# nixie_drive_neo.net
KiCad netlist of a schematic drawn in EAGLE
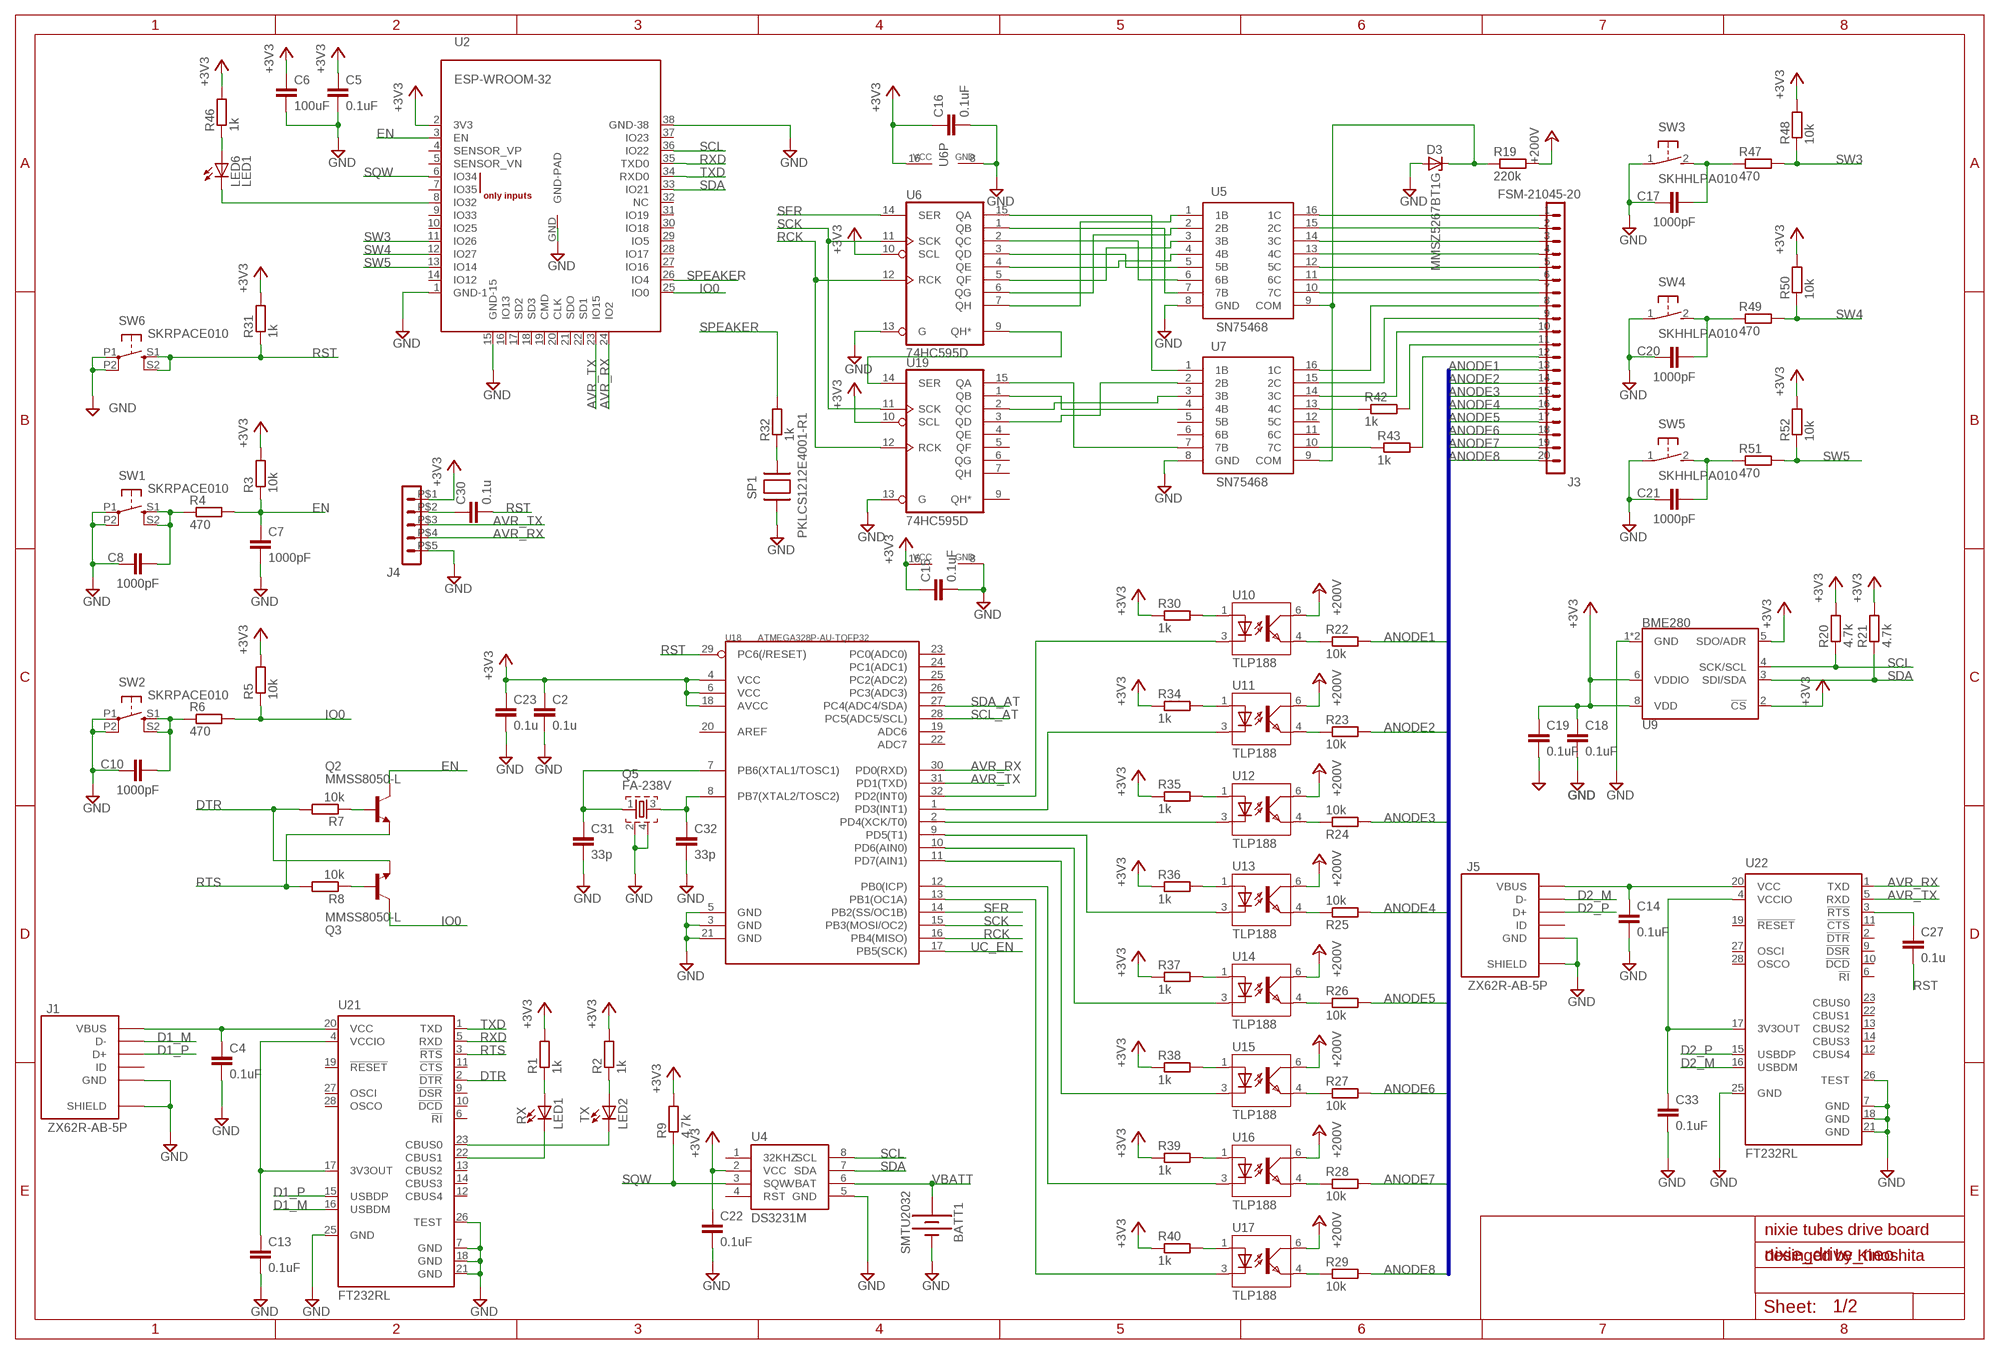
[diagram p0: schematic, sheet 1]
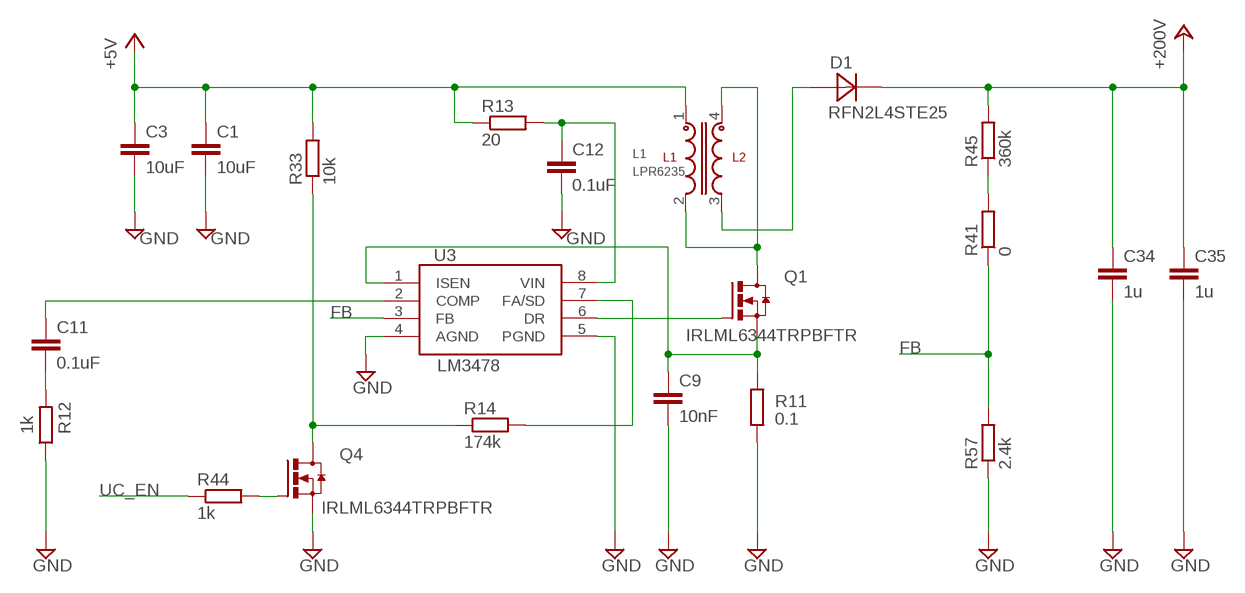
[diagram p1: schematic, sheet 2]

(export (version "E")
  (design (tool "Eeschema 10.0.6"))
  (components
    (comp (ref "BATT1")
      (value "SMTU2032")
      (footprint "eagle-import:SMTU2032")
      (libsource (lib "eagle-import") (part "SMTU2032"))
    )
    (comp (ref "C2")
      (value "0.1u")
      (footprint "eagle-import:C0603")
      (libsource (lib "eagle-import") (part "C-EUC0603"))
    )
    (comp (ref "C4")
      (value "0.1uF")
      (footprint "eagle-import:C0603")
      (libsource (lib "eagle-import") (part "C-EUC0603"))
    )
    (comp (ref "C5")
      (value "0.1uF")
      (footprint "eagle-import:C0603")
      (libsource (lib "eagle-import") (part "C-EUC0603"))
    )
    (comp (ref "C6")
      (value "100uF")
      (footprint "eagle-import:C1210")
      (libsource (lib "eagle-import") (part "C-EUC1210"))
    )
    (comp (ref "C7")
      (value "1000pF")
      (footprint "eagle-import:C0603")
      (libsource (lib "eagle-import") (part "C-EUC0603"))
    )
    (comp (ref "C8")
      (value "1000pF")
      (footprint "eagle-import:C0603")
      (libsource (lib "eagle-import") (part "C-EUC0603"))
    )
    (comp (ref "C10")
      (value "1000pF")
      (footprint "eagle-import:C0603")
      (libsource (lib "eagle-import") (part "C-EUC0603"))
    )
    (comp (ref "C13")
      (value "0.1uF")
      (footprint "eagle-import:C0603")
      (libsource (lib "eagle-import") (part "C-EUC0603"))
    )
    (comp (ref "C14")
      (value "0.1uF")
      (footprint "eagle-import:C0603")
      (libsource (lib "eagle-import") (part "C-EUC0603"))
    )
    (comp (ref "C15")
      (value "0.1uF")
      (footprint "eagle-import:C0603")
      (libsource (lib "eagle-import") (part "C-EUC0603"))
    )
    (comp (ref "C16")
      (value "0.1uF")
      (footprint "eagle-import:C0603")
      (libsource (lib "eagle-import") (part "C-EUC0603"))
    )
    (comp (ref "C17")
      (value "1000pF")
      (footprint "eagle-import:C0603")
      (libsource (lib "eagle-import") (part "C-EUC0603"))
    )
    (comp (ref "C18")
      (value "0.1uF")
      (footprint "eagle-import:C0603")
      (libsource (lib "eagle-import") (part "C-EUC0603"))
    )
    (comp (ref "C19")
      (value "0.1uF")
      (footprint "eagle-import:C0603")
      (libsource (lib "eagle-import") (part "C-EUC0603"))
    )
    (comp (ref "C20")
      (value "1000pF")
      (footprint "eagle-import:C0603")
      (libsource (lib "eagle-import") (part "C-EUC0603"))
    )
    (comp (ref "C21")
      (value "1000pF")
      (footprint "eagle-import:C0603")
      (libsource (lib "eagle-import") (part "C-EUC0603"))
    )
    (comp (ref "C22")
      (value "0.1uF")
      (footprint "eagle-import:C0603")
      (libsource (lib "eagle-import") (part "C-EUC0603"))
    )
    (comp (ref "C23")
      (value "0.1u")
      (footprint "eagle-import:C0603")
      (libsource (lib "eagle-import") (part "C-EUC0603"))
    )
    (comp (ref "C27")
      (value "0.1u")
      (footprint "eagle-import:C0603")
      (libsource (lib "eagle-import") (part "C-EUC0603"))
    )
    (comp (ref "C30")
      (value "0.1u")
      (footprint "eagle-import:C0603")
      (libsource (lib "eagle-import") (part "C-EUC0603"))
    )
    (comp (ref "C31")
      (value "33p")
      (footprint "eagle-import:C0603")
      (libsource (lib "eagle-import") (part "C-EUC0603"))
    )
    (comp (ref "C32")
      (value "33p")
      (footprint "eagle-import:C0603")
      (libsource (lib "eagle-import") (part "C-EUC0603"))
    )
    (comp (ref "C33")
      (value "0.1uF")
      (footprint "eagle-import:C0603")
      (libsource (lib "eagle-import") (part "C-EUC0603"))
    )
    (comp (ref "D3")
      (value "MMSZ5267BT1G")
      (footprint "eagle-import:SOD123")
      (libsource (lib "eagle-import") (part "MMSZ5267BT1G"))
    )
    (comp (ref "J1")
      (value "ZX62R-AB-5P")
      (footprint "eagle-import:ZX62R-B-5PA")
      (libsource (lib "eagle-import") (part "ZX62R-AB-5P"))
    )
    (comp (ref "J3")
      (value "FSM-21045-20")
      (footprint "eagle-import:FSM-21045-20")
      (libsource (lib "eagle-import") (part "FSM-21045-20"))
    )
    (comp (ref "J4")
      (value "PIN_HEADER_MALE_1X05_05P")
      (footprint "eagle-import:PIN_HEADER_MALE_1X05_05P")
      (libsource (lib "eagle-import") (part "PIN_HEADER_MALE_1X05_05P"))
    )
    (comp (ref "J5")
      (value "ZX62R-AB-5P")
      (footprint "eagle-import:ZX62R-B-5PA")
      (libsource (lib "eagle-import") (part "ZX62R-AB-5P"))
    )
    (comp (ref "LED1")
      (value "RX")
      (footprint "eagle-import:CHIPLED_0603")
      (libsource (lib "eagle-import") (part "LEDCHIPLED_0603"))
    )
    (comp (ref "LED2")
      (value "TX")
      (footprint "eagle-import:CHIPLED_0603")
      (libsource (lib "eagle-import") (part "LEDCHIPLED_0603"))
    )
    (comp (ref "LED6")
      (value "LED1")
      (footprint "eagle-import:CHIPLED_0603")
      (libsource (lib "eagle-import") (part "LEDCHIPLED_0603"))
    )
    (comp (ref "Q2")
      (value "MMSS8050-L")
      (footprint "eagle-import:SOT23")
      (libsource (lib "eagle-import") (part "MMSS8050-L"))
    )
    (comp (ref "Q3")
      (value "MMSS8050-L")
      (footprint "eagle-import:SOT23")
      (libsource (lib "eagle-import") (part "MMSS8050-L"))
    )
    (comp (ref "Q5")
      (value "FA-238V")
      (footprint "eagle-import:FA238-V")
      (libsource (lib "eagle-import") (part "FA-238V"))
    )
    (comp (ref "R1")
      (value "1k")
      (footprint "eagle-import:R0603")
      (libsource (lib "eagle-import") (part "taki-library_R-EU_R0603"))
    )
    (comp (ref "R2")
      (value "1k")
      (footprint "eagle-import:R0603")
      (libsource (lib "eagle-import") (part "taki-library_R-EU_R0603"))
    )
    (comp (ref "R3")
      (value "10k")
      (footprint "eagle-import:R0603")
      (libsource (lib "eagle-import") (part "taki-library_R-EU_R0603"))
    )
    (comp (ref "R4")
      (value "470")
      (footprint "eagle-import:R0603")
      (libsource (lib "eagle-import") (part "taki-library_R-EU_R0603"))
    )
    (comp (ref "R5")
      (value "10k")
      (footprint "eagle-import:R0603")
      (libsource (lib "eagle-import") (part "taki-library_R-EU_R0603"))
    )
    (comp (ref "R6")
      (value "470")
      (footprint "eagle-import:R0603")
      (libsource (lib "eagle-import") (part "taki-library_R-EU_R0603"))
    )
    (comp (ref "R7")
      (value "10k")
      (footprint "eagle-import:R0603")
      (libsource (lib "eagle-import") (part "taki-library_R-EU_R0603"))
    )
    (comp (ref "R8")
      (value "10k")
      (footprint "eagle-import:R0603")
      (libsource (lib "eagle-import") (part "taki-library_R-EU_R0603"))
    )
    (comp (ref "R9")
      (value "4.7k")
      (footprint "eagle-import:R0603")
      (libsource (lib "eagle-import") (part "taki-library_R-EU_R0603"))
    )
    (comp (ref "R19")
      (value "220k")
      (footprint "eagle-import:R0603")
      (libsource (lib "eagle-import") (part "taki-library_R-EU_R0603"))
    )
    (comp (ref "R20")
      (value "4.7k")
      (footprint "eagle-import:R0603")
      (libsource (lib "eagle-import") (part "taki-library_R-EU_R0603"))
    )
    (comp (ref "R21")
      (value "4.7k")
      (footprint "eagle-import:R0603")
      (libsource (lib "eagle-import") (part "taki-library_R-EU_R0603"))
    )
    (comp (ref "R22")
      (value "10k")
      (footprint "eagle-import:R3216")
      (libsource (lib "eagle-import") (part "taki-library_R-EU_R3216"))
    )
    (comp (ref "R23")
      (value "10k")
      (footprint "eagle-import:R3216")
      (libsource (lib "eagle-import") (part "taki-library_R-EU_R3216"))
    )
    (comp (ref "R24")
      (value "10k")
      (footprint "eagle-import:R3216")
      (libsource (lib "eagle-import") (part "taki-library_R-EU_R3216"))
    )
    (comp (ref "R25")
      (value "10k")
      (footprint "eagle-import:R3216")
      (libsource (lib "eagle-import") (part "taki-library_R-EU_R3216"))
    )
    (comp (ref "R26")
      (value "10k")
      (footprint "eagle-import:R3216")
      (libsource (lib "eagle-import") (part "taki-library_R-EU_R3216"))
    )
    (comp (ref "R27")
      (value "10k")
      (footprint "eagle-import:R3216")
      (libsource (lib "eagle-import") (part "taki-library_R-EU_R3216"))
    )
    (comp (ref "R28")
      (value "10k")
      (footprint "eagle-import:R3216")
      (libsource (lib "eagle-import") (part "taki-library_R-EU_R3216"))
    )
    (comp (ref "R29")
      (value "10k")
      (footprint "eagle-import:R3216")
      (libsource (lib "eagle-import") (part "taki-library_R-EU_R3216"))
    )
    (comp (ref "R30")
      (value "1k")
      (footprint "eagle-import:R0603")
      (libsource (lib "eagle-import") (part "R-EU_R0603"))
    )
    (comp (ref "R31")
      (value "1k")
      (footprint "eagle-import:R0603")
      (libsource (lib "eagle-import") (part "taki-library_R-EU_R0603"))
    )
    (comp (ref "R32")
      (value "1k")
      (footprint "eagle-import:R0603")
      (libsource (lib "eagle-import") (part "taki-library_R-EU_R0603"))
    )
    (comp (ref "R34")
      (value "1k")
      (footprint "eagle-import:R0603")
      (libsource (lib "eagle-import") (part "R-EU_R0603"))
    )
    (comp (ref "R35")
      (value "1k")
      (footprint "eagle-import:R0603")
      (libsource (lib "eagle-import") (part "R-EU_R0603"))
    )
    (comp (ref "R36")
      (value "1k")
      (footprint "eagle-import:R0603")
      (libsource (lib "eagle-import") (part "R-EU_R0603"))
    )
    (comp (ref "R37")
      (value "1k")
      (footprint "eagle-import:R0603")
      (libsource (lib "eagle-import") (part "R-EU_R0603"))
    )
    (comp (ref "R38")
      (value "1k")
      (footprint "eagle-import:R0603")
      (libsource (lib "eagle-import") (part "R-EU_R0603"))
    )
    (comp (ref "R39")
      (value "1k")
      (footprint "eagle-import:R0603")
      (libsource (lib "eagle-import") (part "R-EU_R0603"))
    )
    (comp (ref "R40")
      (value "1k")
      (footprint "eagle-import:R0603")
      (libsource (lib "eagle-import") (part "R-EU_R0603"))
    )
    (comp (ref "R42")
      (value "1k")
      (footprint "eagle-import:R0603")
      (libsource (lib "eagle-import") (part "R-EU_R0603"))
    )
    (comp (ref "R43")
      (value "1k")
      (footprint "eagle-import:R0603")
      (libsource (lib "eagle-import") (part "R-EU_R0603"))
    )
    (comp (ref "R46")
      (value "1k")
      (footprint "eagle-import:R0603")
      (libsource (lib "eagle-import") (part "taki-library_R-EU_R0603"))
    )
    (comp (ref "R47")
      (value "470")
      (footprint "eagle-import:R0603")
      (libsource (lib "eagle-import") (part "taki-library_R-EU_R0603"))
    )
    (comp (ref "R48")
      (value "10k")
      (footprint "eagle-import:R0603")
      (libsource (lib "eagle-import") (part "taki-library_R-EU_R0603"))
    )
    (comp (ref "R49")
      (value "470")
      (footprint "eagle-import:R0603")
      (libsource (lib "eagle-import") (part "taki-library_R-EU_R0603"))
    )
    (comp (ref "R50")
      (value "10k")
      (footprint "eagle-import:R0603")
      (libsource (lib "eagle-import") (part "taki-library_R-EU_R0603"))
    )
    (comp (ref "R51")
      (value "470")
      (footprint "eagle-import:R0603")
      (libsource (lib "eagle-import") (part "taki-library_R-EU_R0603"))
    )
    (comp (ref "R52")
      (value "10k")
      (footprint "eagle-import:R0603")
      (libsource (lib "eagle-import") (part "taki-library_R-EU_R0603"))
    )
    (comp (ref "SP1")
      (value "PKLCS1212E4001-R1")
      (footprint "eagle-import:PKLCS1212E4001-R1")
      (libsource (lib "eagle-import") (part "PKLCS1212E4001-R1"))
    )
    (comp (ref "SW1")
      (value "SKRPACE010")
      (footprint "eagle-import:SKRPACE010")
      (libsource (lib "eagle-import") (part "SKRPACE010"))
    )
    (comp (ref "SW2")
      (value "SKRPACE010")
      (footprint "eagle-import:SKRPACE010")
      (libsource (lib "eagle-import") (part "SKRPACE010"))
    )
    (comp (ref "SW3")
      (value "SKHHLPA010")
      (footprint "eagle-import:SKHHLPA010")
      (libsource (lib "eagle-import") (part "SKHHLPA010"))
    )
    (comp (ref "SW4")
      (value "SKHHLPA010")
      (footprint "eagle-import:SKHHLPA010")
      (libsource (lib "eagle-import") (part "SKHHLPA010"))
    )
    (comp (ref "SW5")
      (value "SKHHLPA010")
      (footprint "eagle-import:SKHHLPA010")
      (libsource (lib "eagle-import") (part "SKHHLPA010"))
    )
    (comp (ref "SW6")
      (value "SKRPACE010")
      (footprint "eagle-import:SKRPACE010")
      (libsource (lib "eagle-import") (part "SKRPACE010"))
    )
    (comp (ref "U2")
      (value "ESP-WROOM-32")
      (footprint "eagle-import:ESP-WROOM-32")
      (libsource (lib "eagle-import") (part "ESP-WROOM-32"))
    )
    (comp (ref "U4")
      (value "DS3231M")
      (footprint "eagle-import:SO08")
      (libsource (lib "eagle-import") (part "DS3231M"))
    )
    (comp (ref "U5")
      (value "SN75468")
      (footprint "eagle-import:R-PDSO-G16")
      (libsource (lib "eagle-import") (part "SN75468"))
    )
    (comp (ref "U6")
      (value "74HC595D")
      (footprint "eagle-import:SO16")
      (libsource (lib "eagle-import") (part "74595DHC"))
    )
    (comp (ref "U7")
      (value "SN75468")
      (footprint "eagle-import:R-PDSO-G16")
      (libsource (lib "eagle-import") (part "SN75468"))
    )
    (comp (ref "U9")
      (value "BME280")
      (footprint "eagle-import:LGA-8-2.5X2.5")
      (libsource (lib "eagle-import") (part "BME280"))
    )
    (comp (ref "U10")
      (value "TLP188")
      (footprint "eagle-import:11-4M1S")
      (libsource (lib "eagle-import") (part "TLP188"))
    )
    (comp (ref "U11")
      (value "TLP188")
      (footprint "eagle-import:11-4M1S")
      (libsource (lib "eagle-import") (part "TLP188"))
    )
    (comp (ref "U12")
      (value "TLP188")
      (footprint "eagle-import:11-4M1S")
      (libsource (lib "eagle-import") (part "TLP188"))
    )
    (comp (ref "U13")
      (value "TLP188")
      (footprint "eagle-import:11-4M1S")
      (libsource (lib "eagle-import") (part "TLP188"))
    )
    (comp (ref "U14")
      (value "TLP188")
      (footprint "eagle-import:11-4M1S")
      (libsource (lib "eagle-import") (part "TLP188"))
    )
    (comp (ref "U15")
      (value "TLP188")
      (footprint "eagle-import:11-4M1S")
      (libsource (lib "eagle-import") (part "TLP188"))
    )
    (comp (ref "U16")
      (value "TLP188")
      (footprint "eagle-import:11-4M1S")
      (libsource (lib "eagle-import") (part "TLP188"))
    )
    (comp (ref "U17")
      (value "TLP188")
      (footprint "eagle-import:11-4M1S")
      (libsource (lib "eagle-import") (part "TLP188"))
    )
    (comp (ref "U18")
      (value "ATMEGA328P-AU-TQFP32")
      (footprint "eagle-import:TQFP32-0.8-7X7MM")
      (fields (field (name "MPN") "ATMEGA328P-AU"))
      (libsource (lib "eagle-import") (part "MCU-ATMEGA328P-AU(TQFP32)"))
    )
    (comp (ref "U19")
      (value "74HC595D")
      (footprint "eagle-import:SO16")
      (libsource (lib "eagle-import") (part "74595DHC"))
    )
    (comp (ref "U21")
      (value "FT232RL")
      (footprint "eagle-import:SSOP28")
      (libsource (lib "eagle-import") (part "FT232RL"))
    )
    (comp (ref "U22")
      (value "FT232RL")
      (footprint "eagle-import:SSOP28")
      (libsource (lib "eagle-import") (part "FT232RL"))
    )
    (comp (ref "C1")
      (value "10uF")
      (footprint "eagle-import:C0603")
      (libsource (lib "eagle-import") (part "C-EUC0603"))
    )
    (comp (ref "C3")
      (value "10uF")
      (footprint "eagle-import:C0603")
      (libsource (lib "eagle-import") (part "C-EUC0603"))
    )
    (comp (ref "C9")
      (value "10nF")
      (footprint "eagle-import:C0603")
      (libsource (lib "eagle-import") (part "C-EUC0603"))
    )
    (comp (ref "C11")
      (value "0.1uF")
      (footprint "eagle-import:C0603")
      (libsource (lib "eagle-import") (part "C-EUC0603"))
    )
    (comp (ref "C12")
      (value "0.1uF")
      (footprint "eagle-import:C0603")
      (libsource (lib "eagle-import") (part "C-EUC0603"))
    )
    (comp (ref "C34")
      (value "1u")
      (footprint "eagle-import:C5750")
      (libsource (lib "eagle-import") (part "C-EU"))
    )
    (comp (ref "C35")
      (value "1u")
      (footprint "eagle-import:C5750")
      (libsource (lib "eagle-import") (part "C-EU"))
    )
    (comp (ref "D1")
      (value "RFN2L4STE25")
      (footprint "eagle-import:SOD-106")
      (libsource (lib "eagle-import") (part "RFN2L4STE25"))
    )
    (comp (ref "L1")
      (value "LPR6235")
      (footprint "eagle-import:LPR6235")
      (libsource (lib "eagle-import") (part "LPR6235"))
    )
    (comp (ref "Q1")
      (value "IRLML6344TRPBFTR")
      (footprint "eagle-import:SOT23-N-MOSFET")
      (libsource (lib "eagle-import") (part "IRLML6344TRPBFTR"))
    )
    (comp (ref "Q4")
      (value "IRLML6344TRPBFTR")
      (footprint "eagle-import:SOT23-N-MOSFET")
      (libsource (lib "eagle-import") (part "IRLML6344TRPBFTR"))
    )
    (comp (ref "R11")
      (value "0.1")
      (footprint "eagle-import:R0603")
      (libsource (lib "eagle-import") (part "taki-library_R-EU_R0603"))
    )
    (comp (ref "R12")
      (value "1k")
      (footprint "eagle-import:R0603")
      (libsource (lib "eagle-import") (part "taki-library_R-EU_R0603"))
    )
    (comp (ref "R13")
      (value "20")
      (footprint "eagle-import:R0603")
      (libsource (lib "eagle-import") (part "taki-library_R-EU_R0603"))
    )
    (comp (ref "R14")
      (value "174k")
      (footprint "eagle-import:R0603")
      (libsource (lib "eagle-import") (part "taki-library_R-EU_R0603"))
    )
    (comp (ref "R33")
      (value "10k")
      (footprint "eagle-import:R0603")
      (libsource (lib "eagle-import") (part "taki-library_R-EU_R0603"))
    )
    (comp (ref "R41")
      (value "0")
      (footprint "eagle-import:R0603")
      (libsource (lib "eagle-import") (part "taki-library_R-EU_R0603"))
    )
    (comp (ref "R44")
      (value "1k")
      (footprint "eagle-import:R0603")
      (libsource (lib "eagle-import") (part "taki-library_R-EU_R0603"))
    )
    (comp (ref "R45")
      (value "360k")
      (footprint "eagle-import:R0603")
      (libsource (lib "eagle-import") (part "taki-library_R-EU_R0603"))
    )
    (comp (ref "R57")
      (value "2.4k")
      (footprint "eagle-import:R0603")
      (libsource (lib "eagle-import") (part "taki-library_R-EU_R0603"))
    )
    (comp (ref "U3")
      (value "LM3478")
      (footprint "eagle-import:SOIC8-LT")
      (libsource (lib "eagle-import") (part "LM3478"))
    )
  )
  (nets
    (net (code "1") (name "+3V3") (class "Default")
      (node (ref "C15") (pin "1") (pinfunction "1_1") (pintype "passive"))
      (node (ref "C16") (pin "1") (pinfunction "1_1") (pintype "passive"))
      (node (ref "C18") (pin "1") (pinfunction "1_1") (pintype "passive"))
      (node (ref "C19") (pin "1") (pinfunction "1_1") (pintype "passive"))
      (node (ref "C2") (pin "1") (pinfunction "1_1") (pintype "passive"))
      (node (ref "C22") (pin "1") (pinfunction "1_1") (pintype "passive"))
      (node (ref "C23") (pin "1") (pinfunction "1_1") (pintype "passive"))
      (node (ref "C5") (pin "1") (pinfunction "1_1") (pintype "passive"))
      (node (ref "C6") (pin "1") (pinfunction "1_1") (pintype "passive"))
      (node (ref "J4") (pin "P$1") (pinfunction "1_P$1") (pintype "bidirectional"))
      (node (ref "R1") (pin "2") (pinfunction "2_2") (pintype "passive"))
      (node (ref "R2") (pin "2") (pinfunction "2_2") (pintype "passive"))
      (node (ref "R20") (pin "2") (pinfunction "2_2") (pintype "passive"))
      (node (ref "R21") (pin "2") (pinfunction "2_2") (pintype "passive"))
      (node (ref "R3") (pin "2") (pinfunction "2_2") (pintype "passive"))
      (node (ref "R30") (pin "1") (pinfunction "1_1") (pintype "passive"))
      (node (ref "R31") (pin "2") (pinfunction "2_2") (pintype "passive"))
      (node (ref "R34") (pin "1") (pinfunction "1_1") (pintype "passive"))
      (node (ref "R35") (pin "1") (pinfunction "1_1") (pintype "passive"))
      (node (ref "R36") (pin "1") (pinfunction "1_1") (pintype "passive"))
      (node (ref "R37") (pin "1") (pinfunction "1_1") (pintype "passive"))
      (node (ref "R38") (pin "1") (pinfunction "1_1") (pintype "passive"))
      (node (ref "R39") (pin "1") (pinfunction "1_1") (pintype "passive"))
      (node (ref "R40") (pin "1") (pinfunction "1_1") (pintype "passive"))
      (node (ref "R46") (pin "2") (pinfunction "2_2") (pintype "passive"))
      (node (ref "R48") (pin "2") (pinfunction "2_2") (pintype "passive"))
      (node (ref "R5") (pin "2") (pinfunction "2_2") (pintype "passive"))
      (node (ref "R50") (pin "2") (pinfunction "2_2") (pintype "passive"))
      (node (ref "R52") (pin "2") (pinfunction "2_2") (pintype "passive"))
      (node (ref "R9") (pin "2") (pinfunction "2_2") (pintype "passive"))
      (node (ref "U18") (pin "18") (pinfunction "AVCC_18") (pintype "bidirectional"))
      (node (ref "U18") (pin "4") (pinfunction "VCC_4") (pintype "bidirectional"))
      (node (ref "U18") (pin "6") (pinfunction "VCC_6") (pintype "bidirectional"))
      (node (ref "U19") (pin "10") (pinfunction "SCL_10") (pintype "input"))
      (node (ref "U19") (pin "16") (pinfunction "VCC_16") (pintype "power_in"))
      (node (ref "U2") (pin "2") (pinfunction "3V3_2") (pintype "bidirectional"))
      (node (ref "U4") (pin "2") (pinfunction "VCC_2") (pintype "power_in"))
      (node (ref "U6") (pin "10") (pinfunction "SCL_10") (pintype "input"))
      (node (ref "U6") (pin "16") (pinfunction "VCC_16") (pintype "power_in"))
      (node (ref "U9") (pin "2") (pinfunction "~{CS}_2") (pintype "bidirectional"))
      (node (ref "U9") (pin "5") (pinfunction "SDO/ADR_5") (pintype "bidirectional"))
      (node (ref "U9") (pin "6") (pinfunction "VDDIO_6") (pintype "bidirectional"))
      (node (ref "U9") (pin "8") (pinfunction "VDD_8") (pintype "bidirectional"))
    )
    (net (code "2") (name "+5V") (class "Default")
      (node (ref "C1") (pin "1") (pinfunction "1_1") (pintype "passive"))
      (node (ref "C3") (pin "1") (pinfunction "1_1") (pintype "passive"))
      (node (ref "L1") (pin "1") (pinfunction "1_1") (pintype "bidirectional"))
      (node (ref "R13") (pin "1") (pinfunction "1_1") (pintype "passive"))
      (node (ref "R33") (pin "2") (pinfunction "2_2") (pintype "passive"))
    )
    (net (code "3") (name "+200V") (class "Default")
      (node (ref "C34") (pin "1") (pinfunction "1_1") (pintype "passive"))
      (node (ref "C35") (pin "1") (pinfunction "1_1") (pintype "passive"))
      (node (ref "D1") (pin "K") (pinfunction "C_K") (pintype "passive"))
      (node (ref "R19") (pin "2") (pinfunction "2_2") (pintype "passive"))
      (node (ref "R45") (pin "2") (pinfunction "2_2") (pintype "passive"))
      (node (ref "U10") (pin "6") (pinfunction "COL_6") (pintype "passive"))
      (node (ref "U11") (pin "6") (pinfunction "COL_6") (pintype "passive"))
      (node (ref "U12") (pin "6") (pinfunction "COL_6") (pintype "passive"))
      (node (ref "U13") (pin "6") (pinfunction "COL_6") (pintype "passive"))
      (node (ref "U14") (pin "6") (pinfunction "COL_6") (pintype "passive"))
      (node (ref "U15") (pin "6") (pinfunction "COL_6") (pintype "passive"))
      (node (ref "U16") (pin "6") (pinfunction "COL_6") (pintype "passive"))
      (node (ref "U17") (pin "6") (pinfunction "COL_6") (pintype "passive"))
    )
    (net (code "4") (name "ANODE1") (class "Default")
      (node (ref "J3") (pin "13") (pinfunction "13_13") (pintype "bidirectional"))
      (node (ref "R22") (pin "2") (pinfunction "2_2") (pintype "passive"))
    )
    (net (code "5") (name "ANODE2") (class "Default")
      (node (ref "J3") (pin "14") (pinfunction "14_14") (pintype "bidirectional"))
      (node (ref "R23") (pin "2") (pinfunction "2_2") (pintype "passive"))
    )
    (net (code "6") (name "ANODE3") (class "Default")
      (node (ref "J3") (pin "15") (pinfunction "15_15") (pintype "bidirectional"))
      (node (ref "R24") (pin "2") (pinfunction "2_2") (pintype "passive"))
    )
    (net (code "7") (name "ANODE4") (class "Default")
      (node (ref "J3") (pin "16") (pinfunction "16_16") (pintype "bidirectional"))
      (node (ref "R25") (pin "2") (pinfunction "2_2") (pintype "passive"))
    )
    (net (code "8") (name "ANODE5") (class "Default")
      (node (ref "J3") (pin "17") (pinfunction "17_17") (pintype "bidirectional"))
      (node (ref "R26") (pin "2") (pinfunction "2_2") (pintype "passive"))
    )
    (net (code "9") (name "ANODE6") (class "Default")
      (node (ref "J3") (pin "18") (pinfunction "18_18") (pintype "bidirectional"))
      (node (ref "R27") (pin "2") (pinfunction "2_2") (pintype "passive"))
    )
    (net (code "10") (name "ANODE7") (class "Default")
      (node (ref "J3") (pin "19") (pinfunction "19_19") (pintype "bidirectional"))
      (node (ref "R28") (pin "2") (pinfunction "2_2") (pintype "passive"))
    )
    (net (code "11") (name "ANODE8") (class "Default")
      (node (ref "J3") (pin "20") (pinfunction "20_20") (pintype "bidirectional"))
      (node (ref "R29") (pin "2") (pinfunction "2_2") (pintype "passive"))
    )
    (net (code "12") (name "AVR_RX") (class "Default")
      (node (ref "J4") (pin "P$4") (pinfunction "4_P$4") (pintype "bidirectional"))
      (node (ref "U18") (pin "30") (pinfunction "PD0(RXD)_30") (pintype "bidirectional"))
      (node (ref "U2") (pin "24") (pinfunction "IO2_24") (pintype "bidirectional"))
      (node (ref "U22") (pin "1") (pinfunction "TXD_1") (pintype "output"))
    )
    (net (code "13") (name "AVR_TX") (class "Default")
      (node (ref "J4") (pin "P$3") (pinfunction "3_P$3") (pintype "bidirectional"))
      (node (ref "U18") (pin "31") (pinfunction "PD1(TXD)_31") (pintype "bidirectional"))
      (node (ref "U2") (pin "23") (pinfunction "IO15_23") (pintype "bidirectional"))
      (node (ref "U22") (pin "5") (pinfunction "RXD_5") (pintype "input"))
    )
    (net (code "14") (name "D1_M") (class "Default")
      (node (ref "J1") (pin "D-") (pinfunction "D-_D-") (pintype "bidirectional"))
      (node (ref "U21") (pin "16") (pinfunction "USBDM_16") (pintype "bidirectional"))
    )
    (net (code "15") (name "D1_P") (class "Default")
      (node (ref "J1") (pin "D+") (pinfunction "D+_D+") (pintype "bidirectional"))
      (node (ref "U21") (pin "15") (pinfunction "USBDP_15") (pintype "bidirectional"))
    )
    (net (code "16") (name "D2_M") (class "Default")
      (node (ref "J5") (pin "D-") (pinfunction "D-_D-") (pintype "bidirectional"))
      (node (ref "U22") (pin "16") (pinfunction "USBDM_16") (pintype "bidirectional"))
    )
    (net (code "17") (name "D2_P") (class "Default")
      (node (ref "J5") (pin "D+") (pinfunction "D+_D+") (pintype "bidirectional"))
      (node (ref "U22") (pin "15") (pinfunction "USBDP_15") (pintype "bidirectional"))
    )
    (net (code "18") (name "DTR") (class "Default")
      (node (ref "Q3") (pin "E") (pinfunction "E_E") (pintype "passive"))
      (node (ref "R7") (pin "2") (pinfunction "2_2") (pintype "passive"))
      (node (ref "U21") (pin "2") (pinfunction "~{DTR}_2") (pintype "output"))
    )
    (net (code "19") (name "EN") (class "Default")
      (node (ref "C7") (pin "1") (pinfunction "1_1") (pintype "passive"))
      (node (ref "Q2") (pin "C") (pinfunction "C_C") (pintype "passive"))
      (node (ref "R3") (pin "1") (pinfunction "1_1") (pintype "passive"))
      (node (ref "R4") (pin "2") (pinfunction "2_2") (pintype "passive"))
      (node (ref "U2") (pin "3") (pinfunction "EN_3") (pintype "bidirectional"))
    )
    (net (code "20") (name "FB") (class "Default")
      (node (ref "R41") (pin "1") (pinfunction "1_1") (pintype "passive"))
      (node (ref "R57") (pin "2") (pinfunction "2_2") (pintype "passive"))
      (node (ref "U3") (pin "3") (pinfunction "FB_3") (pintype "bidirectional"))
    )
    (net (code "21") (name "GND") (class "Default")
      (node (ref "BATT1") (pin "N") (pinfunction "-_N") (pintype "power_in"))
      (node (ref "C1") (pin "2") (pinfunction "2_2") (pintype "passive"))
      (node (ref "C10") (pin "1") (pinfunction "1_1") (pintype "passive"))
      (node (ref "C12") (pin "2") (pinfunction "2_2") (pintype "passive"))
      (node (ref "C13") (pin "2") (pinfunction "2_2") (pintype "passive"))
      (node (ref "C14") (pin "2") (pinfunction "2_2") (pintype "passive"))
      (node (ref "C15") (pin "2") (pinfunction "2_2") (pintype "passive"))
      (node (ref "C16") (pin "2") (pinfunction "2_2") (pintype "passive"))
      (node (ref "C17") (pin "1") (pinfunction "1_1") (pintype "passive"))
      (node (ref "C18") (pin "2") (pinfunction "2_2") (pintype "passive"))
      (node (ref "C19") (pin "2") (pinfunction "2_2") (pintype "passive"))
      (node (ref "C2") (pin "2") (pinfunction "2_2") (pintype "passive"))
      (node (ref "C20") (pin "1") (pinfunction "1_1") (pintype "passive"))
      (node (ref "C21") (pin "1") (pinfunction "1_1") (pintype "passive"))
      (node (ref "C22") (pin "2") (pinfunction "2_2") (pintype "passive"))
      (node (ref "C23") (pin "2") (pinfunction "2_2") (pintype "passive"))
      (node (ref "C3") (pin "2") (pinfunction "2_2") (pintype "passive"))
      (node (ref "C31") (pin "2") (pinfunction "2_2") (pintype "passive"))
      (node (ref "C32") (pin "2") (pinfunction "2_2") (pintype "passive"))
      (node (ref "C33") (pin "2") (pinfunction "2_2") (pintype "passive"))
      (node (ref "C34") (pin "2") (pinfunction "2_2") (pintype "passive"))
      (node (ref "C35") (pin "2") (pinfunction "2_2") (pintype "passive"))
      (node (ref "C4") (pin "2") (pinfunction "2_2") (pintype "passive"))
      (node (ref "C5") (pin "2") (pinfunction "2_2") (pintype "passive"))
      (node (ref "C6") (pin "2") (pinfunction "2_2") (pintype "passive"))
      (node (ref "C7") (pin "2") (pinfunction "2_2") (pintype "passive"))
      (node (ref "C8") (pin "1") (pinfunction "1_1") (pintype "passive"))
      (node (ref "C9") (pin "2") (pinfunction "2_2") (pintype "passive"))
      (node (ref "D3") (pin "A") (pinfunction "A_A") (pintype "passive"))
      (node (ref "J1") (pin "GND") (pinfunction "GND_GND") (pintype "bidirectional"))
      (node (ref "J1") (pin "SHIELD@1") (pinfunction "SHIELD_SHIELD@1") (pintype "bidirectional"))
      (node (ref "J1") (pin "SHIELD@2") (pinfunction "SHIELD_SHIELD@2") (pintype "bidirectional"))
      (node (ref "J1") (pin "SHIELD@3") (pinfunction "SHIELD_SHIELD@3") (pintype "bidirectional"))
      (node (ref "J1") (pin "SHIELD@4") (pinfunction "SHIELD_SHIELD@4") (pintype "bidirectional"))
      (node (ref "J4") (pin "P$5") (pinfunction "5_P$5") (pintype "bidirectional"))
      (node (ref "J5") (pin "GND") (pinfunction "GND_GND") (pintype "bidirectional"))
      (node (ref "J5") (pin "SHIELD@1") (pinfunction "SHIELD_SHIELD@1") (pintype "bidirectional"))
      (node (ref "J5") (pin "SHIELD@2") (pinfunction "SHIELD_SHIELD@2") (pintype "bidirectional"))
      (node (ref "J5") (pin "SHIELD@3") (pinfunction "SHIELD_SHIELD@3") (pintype "bidirectional"))
      (node (ref "J5") (pin "SHIELD@4") (pinfunction "SHIELD_SHIELD@4") (pintype "bidirectional"))
      (node (ref "Q4") (pin "S") (pinfunction "S_S") (pintype "passive"))
      (node (ref "Q5") (pin "2") (pinfunction "2_2") (pintype "passive"))
      (node (ref "Q5") (pin "4") (pinfunction "4_4") (pintype "passive"))
      (node (ref "R11") (pin "1") (pinfunction "1_1") (pintype "passive"))
      (node (ref "R12") (pin "1") (pinfunction "1_1") (pintype "passive"))
      (node (ref "R57") (pin "1") (pinfunction "1_1") (pintype "passive"))
      (node (ref "SP1") (pin "2") (pinfunction "P$2_2") (pintype "bidirectional"))
      (node (ref "SW1") (pin "P1") (pinfunction "P_P1") (pintype "passive"))
      (node (ref "SW1") (pin "P2") (pinfunction "P1_P2") (pintype "passive"))
      (node (ref "SW2") (pin "P1") (pinfunction "P_P1") (pintype "passive"))
      (node (ref "SW2") (pin "P2") (pinfunction "P1_P2") (pintype "passive"))
      (node (ref "SW3") (pin "1") (pinfunction "1_1") (pintype "passive"))
      (node (ref "SW4") (pin "1") (pinfunction "1_1") (pintype "passive"))
      (node (ref "SW5") (pin "1") (pinfunction "1_1") (pintype "passive"))
      (node (ref "SW6") (pin "P1") (pinfunction "P_P1") (pintype "passive"))
      (node (ref "SW6") (pin "P2") (pinfunction "P1_P2") (pintype "passive"))
      (node (ref "U18") (pin "21") (pinfunction "GND_21") (pintype "bidirectional"))
      (node (ref "U18") (pin "3") (pinfunction "GND_3") (pintype "bidirectional"))
      (node (ref "U18") (pin "5") (pinfunction "GND_5") (pintype "bidirectional"))
      (node (ref "U19") (pin "13") (pinfunction "G_13") (pintype "input"))
      (node (ref "U19") (pin "8") (pinfunction "GND_8") (pintype "power_in"))
      (node (ref "U2") (pin "1") (pinfunction "GND-1_1") (pintype "bidirectional"))
      (node (ref "U2") (pin "15") (pinfunction "GND-15_15") (pintype "bidirectional"))
      (node (ref "U2") (pin "38") (pinfunction "GND-38_38") (pintype "bidirectional"))
      (node (ref "U2") (pin "GND") (pinfunction "GND-PAD_GND") (pintype "bidirectional"))
      (node (ref "U21") (pin "18") (pinfunction "GND_18") (pintype "power_in"))
      (node (ref "U21") (pin "21") (pinfunction "GND_21") (pintype "power_in"))
      (node (ref "U21") (pin "25") (pinfunction "GND_25") (pintype "power_in"))
      (node (ref "U21") (pin "26") (pinfunction "TEST_26") (pintype "input"))
      (node (ref "U21") (pin "7") (pinfunction "GND_7") (pintype "power_in"))
      (node (ref "U22") (pin "18") (pinfunction "GND_18") (pintype "power_in"))
      (node (ref "U22") (pin "21") (pinfunction "GND_21") (pintype "power_in"))
      (node (ref "U22") (pin "25") (pinfunction "GND_25") (pintype "power_in"))
      (node (ref "U22") (pin "26") (pinfunction "TEST_26") (pintype "input"))
      (node (ref "U22") (pin "7") (pinfunction "GND_7") (pintype "power_in"))
      (node (ref "U3") (pin "4") (pinfunction "AGND_4") (pintype "bidirectional"))
      (node (ref "U3") (pin "5") (pinfunction "PGND_5") (pintype "bidirectional"))
      (node (ref "U4") (pin "5") (pinfunction "GND_5") (pintype "power_in"))
      (node (ref "U5") (pin "8") (pinfunction "GND_8") (pintype "bidirectional"))
      (node (ref "U6") (pin "13") (pinfunction "G_13") (pintype "input"))
      (node (ref "U6") (pin "8") (pinfunction "GND_8") (pintype "power_in"))
      (node (ref "U7") (pin "8") (pinfunction "GND_8") (pintype "bidirectional"))
      (node (ref "U9") (pin "1") (pinfunction "GND_1") (pintype "bidirectional"))
      (node (ref "U9") (pin "7") (pinfunction "GND_7") (pintype "bidirectional"))
    )
    (net (code "22") (name "IO0") (class "Default")
      (node (ref "Q3") (pin "C") (pinfunction "C_C") (pintype "passive"))
      (node (ref "R5") (pin "1") (pinfunction "1_1") (pintype "passive"))
      (node (ref "R6") (pin "2") (pinfunction "2_2") (pintype "passive"))
      (node (ref "U2") (pin "25") (pinfunction "IO0_25") (pintype "bidirectional"))
    )
    (net (code "23") (name "Net-(C11-Pad2)") (class "Default")
      (node (ref "C11") (pin "2") (pinfunction "2_2") (pintype "passive"))
      (node (ref "R12") (pin "2") (pinfunction "2_2") (pintype "passive"))
    )
    (net (code "24") (name "Net-(C17-Pad2)") (class "Default")
      (node (ref "C17") (pin "2") (pinfunction "2_2") (pintype "passive"))
      (node (ref "R47") (pin "1") (pinfunction "1_1") (pintype "passive"))
      (node (ref "SW3") (pin "2") (pinfunction "2_2") (pintype "passive"))
    )
    (net (code "25") (name "Net-(C20-Pad2)") (class "Default")
      (node (ref "C20") (pin "2") (pinfunction "2_2") (pintype "passive"))
      (node (ref "R49") (pin "1") (pinfunction "1_1") (pintype "passive"))
      (node (ref "SW4") (pin "2") (pinfunction "2_2") (pintype "passive"))
    )
    (net (code "26") (name "Net-(C21-Pad2)") (class "Default")
      (node (ref "C21") (pin "2") (pinfunction "2_2") (pintype "passive"))
      (node (ref "R51") (pin "1") (pinfunction "1_1") (pintype "passive"))
      (node (ref "SW5") (pin "2") (pinfunction "2_2") (pintype "passive"))
    )
    (net (code "27") (name "Net-(D1-PadA)") (class "Default")
      (node (ref "D1") (pin "A") (pinfunction "A_A") (pintype "passive"))
      (node (ref "L1") (pin "3") (pinfunction "3_3") (pintype "bidirectional"))
    )
    (net (code "28") (name "Net-(D3-C)") (class "Default")
      (node (ref "D3") (pin "K") (pinfunction "C_K") (pintype "passive"))
      (node (ref "R19") (pin "1") (pinfunction "1_1") (pintype "passive"))
      (node (ref "U5") (pin "9") (pinfunction "COM_9") (pintype "bidirectional"))
      (node (ref "U7") (pin "9") (pinfunction "COM_9") (pintype "bidirectional"))
    )
    (net (code "29") (name "Net-(J1-VBUS)") (class "Default")
      (node (ref "C4") (pin "1") (pinfunction "1_1") (pintype "passive"))
      (node (ref "J1") (pin "VCC") (pinfunction "VBUS_VCC") (pintype "bidirectional"))
      (node (ref "U21") (pin "20") (pinfunction "VCC_20") (pintype "power_in"))
    )
    (net (code "30") (name "Net-(J3-Pad11)") (class "Default")
      (node (ref "J3") (pin "11") (pinfunction "11_11") (pintype "bidirectional"))
      (node (ref "R42") (pin "2") (pinfunction "2_2") (pintype "passive"))
    )
    (net (code "31") (name "Net-(J3-Pad12)") (class "Default")
      (node (ref "J3") (pin "12") (pinfunction "12_12") (pintype "bidirectional"))
      (node (ref "R43") (pin "2") (pinfunction "2_2") (pintype "passive"))
    )
    (net (code "32") (name "Net-(J4-2)") (class "Default")
      (node (ref "C30") (pin "1") (pinfunction "1_1") (pintype "passive"))
      (node (ref "J4") (pin "P$2") (pinfunction "2_P$2") (pintype "bidirectional"))
    )
    (net (code "33") (name "Net-(J5-VBUS)") (class "Default")
      (node (ref "C14") (pin "1") (pinfunction "1_1") (pintype "passive"))
      (node (ref "J5") (pin "VCC") (pinfunction "VBUS_VCC") (pintype "bidirectional"))
      (node (ref "U22") (pin "20") (pinfunction "VCC_20") (pintype "power_in"))
    )
    (net (code "34") (name "Net-(L1-Pad2)") (class "Default")
      (node (ref "L1") (pin "2") (pinfunction "2_2") (pintype "bidirectional"))
      (node (ref "L1") (pin "4") (pinfunction "4_4") (pintype "bidirectional"))
      (node (ref "Q1") (pin "D") (pinfunction "D_D") (pintype "passive"))
    )
    (net (code "35") (name "Net-(LED1-PadA)") (class "Default")
      (node (ref "LED1") (pin "A") (pinfunction "A_A") (pintype "passive"))
      (node (ref "R1") (pin "1") (pinfunction "1_1") (pintype "passive"))
    )
    (net (code "36") (name "Net-(LED2-PadA)") (class "Default")
      (node (ref "LED2") (pin "A") (pinfunction "A_A") (pintype "passive"))
      (node (ref "R2") (pin "1") (pinfunction "1_1") (pintype "passive"))
    )
    (net (code "37") (name "Net-(LED6-PadA)") (class "Default")
      (node (ref "LED6") (pin "A") (pinfunction "A_A") (pintype "passive"))
      (node (ref "R46") (pin "1") (pinfunction "1_1") (pintype "passive"))
    )
    (net (code "38") (name "Net-(Q2-PadB)") (class "Default")
      (node (ref "Q2") (pin "B") (pinfunction "B_B") (pintype "passive"))
      (node (ref "R7") (pin "1") (pinfunction "1_1") (pintype "passive"))
    )
    (net (code "39") (name "Net-(Q3-PadB)") (class "Default")
      (node (ref "Q3") (pin "B") (pinfunction "B_B") (pintype "passive"))
      (node (ref "R8") (pin "1") (pinfunction "1_1") (pintype "passive"))
    )
    (net (code "40") (name "Net-(Q4-PadD)") (class "Default")
      (node (ref "Q4") (pin "D") (pinfunction "D_D") (pintype "passive"))
      (node (ref "R14") (pin "1") (pinfunction "1_1") (pintype "passive"))
      (node (ref "R33") (pin "1") (pinfunction "1_1") (pintype "passive"))
    )
    (net (code "41") (name "Net-(Q4-PadG)") (class "Default")
      (node (ref "Q4") (pin "G") (pinfunction "G_G") (pintype "passive"))
      (node (ref "R44") (pin "2") (pinfunction "2_2") (pintype "passive"))
    )
    (net (code "42") (name "Net-(R32-Pad1)") (class "Default")
      (node (ref "R32") (pin "1") (pinfunction "1_1") (pintype "passive"))
      (node (ref "SP1") (pin "1") (pinfunction "1_1") (pintype "bidirectional"))
    )
    (net (code "43") (name "Net-(R41-Pad2)") (class "Default")
      (node (ref "R41") (pin "2") (pinfunction "2_2") (pintype "passive"))
      (node (ref "R45") (pin "1") (pinfunction "1_1") (pintype "passive"))
    )
    (net (code "44") (name "Net-(SW1-S)") (class "Default")
      (node (ref "C8") (pin "2") (pinfunction "2_2") (pintype "passive"))
      (node (ref "R4") (pin "1") (pinfunction "1_1") (pintype "passive"))
      (node (ref "SW1") (pin "S1") (pinfunction "S_S1") (pintype "passive"))
      (node (ref "SW1") (pin "S2") (pinfunction "S1_S2") (pintype "passive"))
    )
    (net (code "45") (name "Net-(SW2-S)") (class "Default")
      (node (ref "C10") (pin "2") (pinfunction "2_2") (pintype "passive"))
      (node (ref "R6") (pin "1") (pinfunction "1_1") (pintype "passive"))
      (node (ref "SW2") (pin "S1") (pinfunction "S_S1") (pintype "passive"))
      (node (ref "SW2") (pin "S2") (pinfunction "S1_S2") (pintype "passive"))
    )
    (net (code "46") (name "Net-(U2-IO32)") (class "Default")
      (node (ref "LED6") (pin "C") (pinfunction "C_C") (pintype "passive"))
      (node (ref "U2") (pin "8") (pinfunction "IO32_8") (pintype "bidirectional"))
    )
    (net (code "47") (name "Net-(U3-COMP)") (class "Default")
      (node (ref "C11") (pin "1") (pinfunction "1_1") (pintype "passive"))
      (node (ref "U3") (pin "2") (pinfunction "COMP_2") (pintype "bidirectional"))
    )
    (net (code "48") (name "Net-(U3-DR)") (class "Default")
      (node (ref "Q1") (pin "G") (pinfunction "G_G") (pintype "passive"))
      (node (ref "U3") (pin "6") (pinfunction "DR_6") (pintype "bidirectional"))
    )
    (net (code "49") (name "Net-(U3-FA{slash}SD)") (class "Default")
      (node (ref "R14") (pin "2") (pinfunction "2_2") (pintype "passive"))
      (node (ref "U3") (pin "7") (pinfunction "FA/SD_7") (pintype "bidirectional"))
    )
    (net (code "50") (name "Net-(U3-ISEN)") (class "Default")
      (node (ref "C9") (pin "1") (pinfunction "1_1") (pintype "passive"))
      (node (ref "Q1") (pin "S") (pinfunction "S_S") (pintype "passive"))
      (node (ref "R11") (pin "2") (pinfunction "2_2") (pintype "passive"))
      (node (ref "U3") (pin "1") (pinfunction "ISEN_1") (pintype "bidirectional"))
    )
    (net (code "51") (name "Net-(U3-VIN)") (class "Default")
      (node (ref "C12") (pin "1") (pinfunction "1_1") (pintype "passive"))
      (node (ref "R13") (pin "2") (pinfunction "2_2") (pintype "passive"))
      (node (ref "U3") (pin "8") (pinfunction "VIN_8") (pintype "bidirectional"))
    )
    (net (code "52") (name "Net-(U5-1B)") (class "Default")
      (node (ref "U5") (pin "1") (pinfunction "1B_1") (pintype "bidirectional"))
      (node (ref "U6") (pin "7") (pinfunction "QH_7") (pintype "tri_state"))
    )
    (net (code "53") (name "Net-(U5-1C)") (class "Default")
      (node (ref "J3") (pin "1") (pinfunction "1_1") (pintype "bidirectional"))
      (node (ref "U5") (pin "16") (pinfunction "1C_16") (pintype "bidirectional"))
    )
    (net (code "54") (name "Net-(U5-2B)") (class "Default")
      (node (ref "U5") (pin "2") (pinfunction "2B_2") (pintype "bidirectional"))
      (node (ref "U6") (pin "6") (pinfunction "QG_6") (pintype "tri_state"))
    )
    (net (code "55") (name "Net-(U5-2C)") (class "Default")
      (node (ref "J3") (pin "2") (pinfunction "2_2") (pintype "bidirectional"))
      (node (ref "U5") (pin "15") (pinfunction "2C_15") (pintype "bidirectional"))
    )
    (net (code "56") (name "Net-(U5-3B)") (class "Default")
      (node (ref "U5") (pin "3") (pinfunction "3B_3") (pintype "bidirectional"))
      (node (ref "U6") (pin "5") (pinfunction "QF_5") (pintype "tri_state"))
    )
    (net (code "57") (name "Net-(U5-3C)") (class "Default")
      (node (ref "J3") (pin "3") (pinfunction "3_3") (pintype "bidirectional"))
      (node (ref "U5") (pin "14") (pinfunction "3C_14") (pintype "bidirectional"))
    )
    (net (code "58") (name "Net-(U5-4B)") (class "Default")
      (node (ref "U5") (pin "4") (pinfunction "4B_4") (pintype "bidirectional"))
      (node (ref "U6") (pin "4") (pinfunction "QE_4") (pintype "tri_state"))
    )
    (net (code "59") (name "Net-(U5-4C)") (class "Default")
      (node (ref "J3") (pin "4") (pinfunction "4_4") (pintype "bidirectional"))
      (node (ref "U5") (pin "13") (pinfunction "4C_13") (pintype "bidirectional"))
    )
    (net (code "60") (name "Net-(U5-5B)") (class "Default")
      (node (ref "U5") (pin "5") (pinfunction "5B_5") (pintype "bidirectional"))
      (node (ref "U6") (pin "3") (pinfunction "QD_3") (pintype "tri_state"))
    )
    (net (code "61") (name "Net-(U5-5C)") (class "Default")
      (node (ref "J3") (pin "5") (pinfunction "5_5") (pintype "bidirectional"))
      (node (ref "U5") (pin "12") (pinfunction "5C_12") (pintype "bidirectional"))
    )
    (net (code "62") (name "Net-(U5-6B)") (class "Default")
      (node (ref "U5") (pin "6") (pinfunction "6B_6") (pintype "bidirectional"))
      (node (ref "U6") (pin "2") (pinfunction "QC_2") (pintype "tri_state"))
    )
    (net (code "63") (name "Net-(U5-6C)") (class "Default")
      (node (ref "J3") (pin "6") (pinfunction "6_6") (pintype "bidirectional"))
      (node (ref "U5") (pin "11") (pinfunction "6C_11") (pintype "bidirectional"))
    )
    (net (code "64") (name "Net-(U5-7B)") (class "Default")
      (node (ref "U5") (pin "7") (pinfunction "7B_7") (pintype "bidirectional"))
      (node (ref "U6") (pin "1") (pinfunction "QB_1") (pintype "tri_state"))
    )
    (net (code "65") (name "Net-(U5-7C)") (class "Default")
      (node (ref "J3") (pin "7") (pinfunction "7_7") (pintype "bidirectional"))
      (node (ref "U5") (pin "10") (pinfunction "7C_10") (pintype "bidirectional"))
    )
    (net (code "66") (name "Net-(U6A-QA)") (class "Default")
      (node (ref "U6") (pin "15") (pinfunction "QA_15") (pintype "tri_state"))
      (node (ref "U7") (pin "1") (pinfunction "1B_1") (pintype "bidirectional"))
    )
    (net (code "67") (name "Net-(U7-1C)") (class "Default")
      (node (ref "J3") (pin "8") (pinfunction "8_8") (pintype "bidirectional"))
      (node (ref "U7") (pin "16") (pinfunction "1C_16") (pintype "bidirectional"))
    )
    (net (code "68") (name "Net-(U7-2C)") (class "Default")
      (node (ref "J3") (pin "9") (pinfunction "9_9") (pintype "bidirectional"))
      (node (ref "U7") (pin "15") (pinfunction "2C_15") (pintype "bidirectional"))
    )
    (net (code "69") (name "Net-(U7-3C)") (class "Default")
      (node (ref "J3") (pin "10") (pinfunction "10_10") (pintype "bidirectional"))
      (node (ref "U7") (pin "14") (pinfunction "3C_14") (pintype "bidirectional"))
    )
    (net (code "70") (name "Net-(U7-4C)") (class "Default")
      (node (ref "R42") (pin "1") (pinfunction "1_1") (pintype "passive"))
      (node (ref "U7") (pin "13") (pinfunction "4C_13") (pintype "bidirectional"))
    )
    (net (code "71") (name "Net-(U7-7C)") (class "Default")
      (node (ref "R43") (pin "1") (pinfunction "1_1") (pintype "passive"))
      (node (ref "U7") (pin "10") (pinfunction "7C_10") (pintype "bidirectional"))
    )
    (net (code "72") (name "Net-(U10-A)") (class "Default")
      (node (ref "R30") (pin "2") (pinfunction "2_2") (pintype "passive"))
      (node (ref "U10") (pin "1") (pinfunction "A_1") (pintype "passive"))
    )
    (net (code "73") (name "Net-(U10-C)") (class "Default")
      (node (ref "U10") (pin "3") (pinfunction "C_3") (pintype "passive"))
      (node (ref "U18") (pin "32") (pinfunction "PD2(INT0)_32") (pintype "bidirectional"))
    )
    (net (code "74") (name "Net-(U10-EMIT)") (class "Default")
      (node (ref "R22") (pin "1") (pinfunction "1_1") (pintype "passive"))
      (node (ref "U10") (pin "4") (pinfunction "EMIT_4") (pintype "passive"))
    )
    (net (code "75") (name "Net-(U11-A)") (class "Default")
      (node (ref "R34") (pin "2") (pinfunction "2_2") (pintype "passive"))
      (node (ref "U11") (pin "1") (pinfunction "A_1") (pintype "passive"))
    )
    (net (code "76") (name "Net-(U11-C)") (class "Default")
      (node (ref "U11") (pin "3") (pinfunction "C_3") (pintype "passive"))
      (node (ref "U18") (pin "1") (pinfunction "PD3(INT1)_1") (pintype "bidirectional"))
    )
    (net (code "77") (name "Net-(U11-EMIT)") (class "Default")
      (node (ref "R23") (pin "1") (pinfunction "1_1") (pintype "passive"))
      (node (ref "U11") (pin "4") (pinfunction "EMIT_4") (pintype "passive"))
    )
    (net (code "78") (name "Net-(U12-A)") (class "Default")
      (node (ref "R35") (pin "2") (pinfunction "2_2") (pintype "passive"))
      (node (ref "U12") (pin "1") (pinfunction "A_1") (pintype "passive"))
    )
    (net (code "79") (name "Net-(U12-C)") (class "Default")
      (node (ref "U12") (pin "3") (pinfunction "C_3") (pintype "passive"))
      (node (ref "U18") (pin "2") (pinfunction "PD4(XCK/T0)_2") (pintype "bidirectional"))
    )
    (net (code "80") (name "Net-(U12-EMIT)") (class "Default")
      (node (ref "R24") (pin "1") (pinfunction "1_1") (pintype "passive"))
      (node (ref "U12") (pin "4") (pinfunction "EMIT_4") (pintype "passive"))
    )
    (net (code "81") (name "Net-(U13-A)") (class "Default")
      (node (ref "R36") (pin "2") (pinfunction "2_2") (pintype "passive"))
      (node (ref "U13") (pin "1") (pinfunction "A_1") (pintype "passive"))
    )
    (net (code "82") (name "Net-(U13-C)") (class "Default")
      (node (ref "U13") (pin "3") (pinfunction "C_3") (pintype "passive"))
      (node (ref "U18") (pin "9") (pinfunction "PD5(T1)_9") (pintype "bidirectional"))
    )
    (net (code "83") (name "Net-(U13-EMIT)") (class "Default")
      (node (ref "R25") (pin "1") (pinfunction "1_1") (pintype "passive"))
      (node (ref "U13") (pin "4") (pinfunction "EMIT_4") (pintype "passive"))
    )
    (net (code "84") (name "Net-(U14-A)") (class "Default")
      (node (ref "R37") (pin "2") (pinfunction "2_2") (pintype "passive"))
      (node (ref "U14") (pin "1") (pinfunction "A_1") (pintype "passive"))
    )
    (net (code "85") (name "Net-(U14-C)") (class "Default")
      (node (ref "U14") (pin "3") (pinfunction "C_3") (pintype "passive"))
      (node (ref "U18") (pin "10") (pinfunction "PD6(AIN0)_10") (pintype "bidirectional"))
    )
    (net (code "86") (name "Net-(U14-EMIT)") (class "Default")
      (node (ref "R26") (pin "1") (pinfunction "1_1") (pintype "passive"))
      (node (ref "U14") (pin "4") (pinfunction "EMIT_4") (pintype "passive"))
    )
    (net (code "87") (name "Net-(U15-A)") (class "Default")
      (node (ref "R38") (pin "2") (pinfunction "2_2") (pintype "passive"))
      (node (ref "U15") (pin "1") (pinfunction "A_1") (pintype "passive"))
    )
    (net (code "88") (name "Net-(U15-C)") (class "Default")
      (node (ref "U15") (pin "3") (pinfunction "C_3") (pintype "passive"))
      (node (ref "U18") (pin "11") (pinfunction "PD7(AIN1)_11") (pintype "bidirectional"))
    )
    (net (code "89") (name "Net-(U15-EMIT)") (class "Default")
      (node (ref "R27") (pin "1") (pinfunction "1_1") (pintype "passive"))
      (node (ref "U15") (pin "4") (pinfunction "EMIT_4") (pintype "passive"))
    )
    (net (code "90") (name "Net-(U16-A)") (class "Default")
      (node (ref "R39") (pin "2") (pinfunction "2_2") (pintype "passive"))
      (node (ref "U16") (pin "1") (pinfunction "A_1") (pintype "passive"))
    )
    (net (code "91") (name "Net-(U16-C)") (class "Default")
      (node (ref "U16") (pin "3") (pinfunction "C_3") (pintype "passive"))
      (node (ref "U18") (pin "12") (pinfunction "PB0(ICP)_12") (pintype "bidirectional"))
    )
    (net (code "92") (name "Net-(U16-EMIT)") (class "Default")
      (node (ref "R28") (pin "1") (pinfunction "1_1") (pintype "passive"))
      (node (ref "U16") (pin "4") (pinfunction "EMIT_4") (pintype "passive"))
    )
    (net (code "93") (name "Net-(U17-A)") (class "Default")
      (node (ref "R40") (pin "2") (pinfunction "2_2") (pintype "passive"))
      (node (ref "U17") (pin "1") (pinfunction "A_1") (pintype "passive"))
    )
    (net (code "94") (name "Net-(U17-C)") (class "Default")
      (node (ref "U17") (pin "3") (pinfunction "C_3") (pintype "passive"))
      (node (ref "U18") (pin "13") (pinfunction "PB1(OC1A)_13") (pintype "bidirectional"))
    )
    (net (code "95") (name "Net-(U17-EMIT)") (class "Default")
      (node (ref "R29") (pin "1") (pinfunction "1_1") (pintype "passive"))
      (node (ref "U17") (pin "4") (pinfunction "EMIT_4") (pintype "passive"))
    )
    (net (code "96") (name "Net-(U18-PB6(XTAL1{slash}TOSC1))") (class "Default")
      (node (ref "C31") (pin "1") (pinfunction "1_1") (pintype "passive"))
      (node (ref "Q5") (pin "1") (pinfunction "1_1") (pintype "passive"))
      (node (ref "U18") (pin "7") (pinfunction "PB6(XTAL1/TOSC1)_7") (pintype "bidirectional"))
    )
    (net (code "97") (name "Net-(U18-PB7(XTAL2{slash}TOSC2))") (class "Default")
      (node (ref "C32") (pin "1") (pinfunction "1_1") (pintype "passive"))
      (node (ref "Q5") (pin "3") (pinfunction "3_3") (pintype "passive"))
      (node (ref "U18") (pin "8") (pinfunction "PB7(XTAL2/TOSC2)_8") (pintype "bidirectional"))
    )
    (net (code "98") (name "Net-(U19A-QA)") (class "Default")
      (node (ref "U19") (pin "15") (pinfunction "QA_15") (pintype "tri_state"))
      (node (ref "U7") (pin "7") (pinfunction "7B_7") (pintype "bidirectional"))
    )
    (net (code "99") (name "Net-(U19A-QB)") (class "Default")
      (node (ref "U19") (pin "1") (pinfunction "QB_1") (pintype "tri_state"))
      (node (ref "U7") (pin "4") (pinfunction "4B_4") (pintype "bidirectional"))
    )
    (net (code "100") (name "Net-(U19A-QC)") (class "Default")
      (node (ref "U19") (pin "2") (pinfunction "QC_2") (pintype "tri_state"))
      (node (ref "U7") (pin "3") (pinfunction "3B_3") (pintype "bidirectional"))
    )
    (net (code "101") (name "Net-(U19A-QD)") (class "Default")
      (node (ref "U19") (pin "3") (pinfunction "QD_3") (pintype "tri_state"))
      (node (ref "U7") (pin "2") (pinfunction "2B_2") (pintype "bidirectional"))
    )
    (net (code "102") (name "Net-(U19A-SER)") (class "Default")
      (node (ref "U19") (pin "14") (pinfunction "SER_14") (pintype "input"))
      (node (ref "U6") (pin "9") (pinfunction "QH*_9") (pintype "tri_state"))
    )
    (net (code "103") (name "Net-(U21-3V3OUT)") (class "Default")
      (node (ref "C13") (pin "1") (pinfunction "1_1") (pintype "passive"))
      (node (ref "U21") (pin "17") (pinfunction "3V3OUT_17") (pintype "output"))
      (node (ref "U21") (pin "4") (pinfunction "VCCIO_4") (pintype "power_in"))
    )
    (net (code "104") (name "Net-(U21-CBUS0)") (class "Default")
      (node (ref "LED2") (pin "C") (pinfunction "C_C") (pintype "passive"))
      (node (ref "U21") (pin "23") (pinfunction "CBUS0_23") (pintype "bidirectional"))
    )
    (net (code "105") (name "Net-(U21-CBUS1)") (class "Default")
      (node (ref "LED1") (pin "C") (pinfunction "C_C") (pintype "passive"))
      (node (ref "U21") (pin "22") (pinfunction "CBUS1_22") (pintype "bidirectional"))
    )
    (net (code "106") (name "Net-(U22-3V3OUT)") (class "Default")
      (node (ref "C33") (pin "1") (pinfunction "1_1") (pintype "passive"))
      (node (ref "U22") (pin "17") (pinfunction "3V3OUT_17") (pintype "output"))
      (node (ref "U22") (pin "4") (pinfunction "VCCIO_4") (pintype "power_in"))
    )
    (net (code "107") (name "Net-(U22-~{RTS})") (class "Default")
      (node (ref "C27") (pin "1") (pinfunction "1_1") (pintype "passive"))
      (node (ref "U22") (pin "3") (pinfunction "~{RTS}_3") (pintype "output"))
    )
    (net (code "108") (name "RCK") (class "Default")
      (node (ref "U18") (pin "16") (pinfunction "PB4(MISO)_16") (pintype "bidirectional"))
      (node (ref "U19") (pin "12") (pinfunction "RCK_12") (pintype "input"))
      (node (ref "U6") (pin "12") (pinfunction "RCK_12") (pintype "input"))
    )
    (net (code "109") (name "RST") (class "Default")
      (node (ref "C27") (pin "2") (pinfunction "2_2") (pintype "passive"))
      (node (ref "C30") (pin "2") (pinfunction "2_2") (pintype "passive"))
      (node (ref "R31") (pin "1") (pinfunction "1_1") (pintype "passive"))
      (node (ref "SW6") (pin "S1") (pinfunction "S_S1") (pintype "passive"))
      (node (ref "SW6") (pin "S2") (pinfunction "S1_S2") (pintype "passive"))
      (node (ref "U18") (pin "29") (pinfunction "PC6(/RESET)_29") (pintype "bidirectional"))
    )
    (net (code "110") (name "RTS") (class "Default")
      (node (ref "Q2") (pin "E") (pinfunction "E_E") (pintype "passive"))
      (node (ref "R8") (pin "2") (pinfunction "2_2") (pintype "passive"))
      (node (ref "U21") (pin "3") (pinfunction "~{RTS}_3") (pintype "output"))
    )
    (net (code "111") (name "RXD") (class "Default")
      (node (ref "U2") (pin "35") (pinfunction "TXD0_35") (pintype "bidirectional"))
      (node (ref "U21") (pin "5") (pinfunction "RXD_5") (pintype "input"))
    )
    (net (code "112") (name "SCK") (class "Default")
      (node (ref "U18") (pin "15") (pinfunction "PB3(MOSI/OC2)_15") (pintype "bidirectional"))
      (node (ref "U19") (pin "11") (pinfunction "SCK_11") (pintype "input"))
      (node (ref "U6") (pin "11") (pinfunction "SCK_11") (pintype "input"))
    )
    (net (code "113") (name "SCL") (class "Default")
      (node (ref "R20") (pin "1") (pinfunction "1_1") (pintype "passive"))
      (node (ref "U2") (pin "36") (pinfunction "IO22_36") (pintype "bidirectional"))
      (node (ref "U4") (pin "8") (pinfunction "SCL_8") (pintype "bidirectional"))
      (node (ref "U9") (pin "4") (pinfunction "SCK/SCL_4") (pintype "bidirectional"))
    )
    (net (code "114") (name "SCL_AT") (class "Default")
      (node (ref "U18") (pin "28") (pinfunction "PC5(ADC5/SCL)_28") (pintype "bidirectional"))
    )
    (net (code "115") (name "SDA") (class "Default")
      (node (ref "R21") (pin "1") (pinfunction "1_1") (pintype "passive"))
      (node (ref "U2") (pin "33") (pinfunction "IO21_33") (pintype "bidirectional"))
      (node (ref "U4") (pin "7") (pinfunction "SDA_7") (pintype "bidirectional"))
      (node (ref "U9") (pin "3") (pinfunction "SDI/SDA_3") (pintype "bidirectional"))
    )
    (net (code "116") (name "SDA_AT") (class "Default")
      (node (ref "U18") (pin "27") (pinfunction "PC4(ADC4/SDA)_27") (pintype "bidirectional"))
    )
    (net (code "117") (name "SER") (class "Default")
      (node (ref "U18") (pin "14") (pinfunction "PB2(SS/OC1B)_14") (pintype "bidirectional"))
      (node (ref "U6") (pin "14") (pinfunction "SER_14") (pintype "input"))
    )
    (net (code "118") (name "SPEAKER") (class "Default")
      (node (ref "R32") (pin "2") (pinfunction "2_2") (pintype "passive"))
      (node (ref "U2") (pin "26") (pinfunction "IO4_26") (pintype "bidirectional"))
    )
    (net (code "119") (name "SQW") (class "Default")
      (node (ref "R9") (pin "1") (pinfunction "1_1") (pintype "passive"))
      (node (ref "U2") (pin "6") (pinfunction "IO34_6") (pintype "input"))
      (node (ref "U4") (pin "3") (pinfunction "SQW_3") (pintype "output"))
    )
    (net (code "120") (name "SW3") (class "Default")
      (node (ref "R47") (pin "2") (pinfunction "2_2") (pintype "passive"))
      (node (ref "R48") (pin "1") (pinfunction "1_1") (pintype "passive"))
      (node (ref "U2") (pin "11") (pinfunction "IO26_11") (pintype "bidirectional"))
    )
    (net (code "121") (name "SW4") (class "Default")
      (node (ref "R49") (pin "2") (pinfunction "2_2") (pintype "passive"))
      (node (ref "R50") (pin "1") (pinfunction "1_1") (pintype "passive"))
      (node (ref "U2") (pin "12") (pinfunction "IO27_12") (pintype "bidirectional"))
    )
    (net (code "122") (name "SW5") (class "Default")
      (node (ref "R51") (pin "2") (pinfunction "2_2") (pintype "passive"))
      (node (ref "R52") (pin "1") (pinfunction "1_1") (pintype "passive"))
      (node (ref "U2") (pin "13") (pinfunction "IO14_13") (pintype "bidirectional"))
    )
    (net (code "123") (name "TXD") (class "Default")
      (node (ref "U2") (pin "34") (pinfunction "RXD0_34") (pintype "bidirectional"))
      (node (ref "U21") (pin "1") (pinfunction "TXD_1") (pintype "output"))
    )
    (net (code "124") (name "UC_EN") (class "Default")
      (node (ref "R44") (pin "1") (pinfunction "1_1") (pintype "passive"))
      (node (ref "U18") (pin "17") (pinfunction "PB5(SCK)_17") (pintype "bidirectional"))
    )
    (net (code "125") (name "VBATT") (class "Default")
      (node (ref "BATT1") (pin "P") (pinfunction "+_P") (pintype "power_in"))
      (node (ref "U4") (pin "6") (pinfunction "VBAT_6") (pintype "power_in"))
    )
    (net (code "126") (name "unconnected-(J1-PadID)") (class "Default")
      (node (ref "J1") (pin "ID") (pinfunction "ID_ID") (pintype "bidirectional"))
    )
    (net (code "127") (name "unconnected-(J5-PadID)") (class "Default")
      (node (ref "J5") (pin "ID") (pinfunction "ID_ID") (pintype "bidirectional"))
    )
    (net (code "128") (name "unconnected-(U2-CLK-Pad20)") (class "Default")
      (node (ref "U2") (pin "20") (pinfunction "CLK_20") (pintype "bidirectional"))
    )
    (net (code "129") (name "unconnected-(U2-CMD-Pad19)") (class "Default")
      (node (ref "U2") (pin "19") (pinfunction "CMD_19") (pintype "bidirectional"))
    )
    (net (code "130") (name "unconnected-(U2-IO5-Pad29)") (class "Default")
      (node (ref "U2") (pin "29") (pinfunction "IO5_29") (pintype "bidirectional"))
    )
    (net (code "131") (name "unconnected-(U2-IO12-Pad14)") (class "Default")
      (node (ref "U2") (pin "14") (pinfunction "IO12_14") (pintype "bidirectional"))
    )
    (net (code "132") (name "unconnected-(U2-IO13-Pad16)") (class "Default")
      (node (ref "U2") (pin "16") (pinfunction "IO13_16") (pintype "bidirectional"))
    )
    (net (code "133") (name "unconnected-(U2-IO16-Pad27)") (class "Default")
      (node (ref "U2") (pin "27") (pinfunction "IO16_27") (pintype "bidirectional"))
    )
    (net (code "134") (name "unconnected-(U2-IO17-Pad28)") (class "Default")
      (node (ref "U2") (pin "28") (pinfunction "IO17_28") (pintype "bidirectional"))
    )
    (net (code "135") (name "unconnected-(U2-IO18-Pad30)") (class "Default")
      (node (ref "U2") (pin "30") (pinfunction "IO18_30") (pintype "bidirectional"))
    )
    (net (code "136") (name "unconnected-(U2-IO19-Pad31)") (class "Default")
      (node (ref "U2") (pin "31") (pinfunction "IO19_31") (pintype "bidirectional"))
    )
    (net (code "137") (name "unconnected-(U2-IO23-Pad37)") (class "Default")
      (node (ref "U2") (pin "37") (pinfunction "IO23_37") (pintype "bidirectional"))
    )
    (net (code "138") (name "unconnected-(U2-IO25-Pad10)") (class "Default")
      (node (ref "U2") (pin "10") (pinfunction "IO25_10") (pintype "bidirectional"))
    )
    (net (code "139") (name "unconnected-(U2-IO33-Pad9)") (class "Default")
      (node (ref "U2") (pin "9") (pinfunction "IO33_9") (pintype "bidirectional"))
    )
    (net (code "140") (name "unconnected-(U2-IO35-Pad7)") (class "Default")
      (node (ref "U2") (pin "7") (pinfunction "IO35_7") (pintype "input"))
    )
    (net (code "141") (name "unconnected-(U2-NC-Pad32)") (class "Default")
      (node (ref "U2") (pin "32") (pinfunction "NC_32") (pintype "bidirectional"))
    )
    (net (code "142") (name "unconnected-(U2-SD1-Pad22)") (class "Default")
      (node (ref "U2") (pin "22") (pinfunction "SD1_22") (pintype "bidirectional"))
    )
    (net (code "143") (name "unconnected-(U2-SD2-Pad17)") (class "Default")
      (node (ref "U2") (pin "17") (pinfunction "SD2_17") (pintype "bidirectional"))
    )
    (net (code "144") (name "unconnected-(U2-SD3-Pad18)") (class "Default")
      (node (ref "U2") (pin "18") (pinfunction "SD3_18") (pintype "bidirectional"))
    )
    (net (code "145") (name "unconnected-(U2-SDO-Pad21)") (class "Default")
      (node (ref "U2") (pin "21") (pinfunction "SDO_21") (pintype "bidirectional"))
    )
    (net (code "146") (name "unconnected-(U2-SENSOR_VN-Pad5)") (class "Default")
      (node (ref "U2") (pin "5") (pinfunction "SENSOR_VN_5") (pintype "input"))
    )
    (net (code "147") (name "unconnected-(U2-SENSOR_VP-Pad4)") (class "Default")
      (node (ref "U2") (pin "4") (pinfunction "SENSOR_VP_4") (pintype "input"))
    )
    (net (code "148") (name "unconnected-(U4-32KHZ-Pad1)") (class "Default")
      (node (ref "U4") (pin "1") (pinfunction "32KHZ_1") (pintype "output"))
    )
    (net (code "149") (name "unconnected-(U4-RST-Pad4)") (class "Default")
      (node (ref "U4") (pin "4") (pinfunction "RST_4") (pintype "bidirectional"))
    )
    (net (code "150") (name "unconnected-(U7-5B-Pad5)") (class "Default")
      (node (ref "U7") (pin "5") (pinfunction "5B_5") (pintype "bidirectional"))
    )
    (net (code "151") (name "unconnected-(U7-5C-Pad12)") (class "Default")
      (node (ref "U7") (pin "12") (pinfunction "5C_12") (pintype "bidirectional"))
    )
    (net (code "152") (name "unconnected-(U7-6B-Pad6)") (class "Default")
      (node (ref "U7") (pin "6") (pinfunction "6B_6") (pintype "bidirectional"))
    )
    (net (code "153") (name "unconnected-(U7-6C-Pad11)") (class "Default")
      (node (ref "U7") (pin "11") (pinfunction "6C_11") (pintype "bidirectional"))
    )
    (net (code "154") (name "unconnected-(U18-ADC6-Pad19)") (class "Default")
      (node (ref "U18") (pin "19") (pinfunction "ADC6_19") (pintype "bidirectional"))
    )
    (net (code "155") (name "unconnected-(U18-ADC7-Pad22)") (class "Default")
      (node (ref "U18") (pin "22") (pinfunction "ADC7_22") (pintype "bidirectional"))
    )
    (net (code "156") (name "unconnected-(U18-AREF-Pad20)") (class "Default")
      (node (ref "U18") (pin "20") (pinfunction "AREF_20") (pintype "bidirectional"))
    )
    (net (code "157") (name "unconnected-(U18-PC0(ADC0)-Pad23)") (class "Default")
      (node (ref "U18") (pin "23") (pinfunction "PC0(ADC0)_23") (pintype "bidirectional"))
    )
    (net (code "158") (name "unconnected-(U18-PC1(ADC1)-Pad24)") (class "Default")
      (node (ref "U18") (pin "24") (pinfunction "PC1(ADC1)_24") (pintype "bidirectional"))
    )
    (net (code "159") (name "unconnected-(U18-PC2(ADC2)-Pad25)") (class "Default")
      (node (ref "U18") (pin "25") (pinfunction "PC2(ADC2)_25") (pintype "bidirectional"))
    )
    (net (code "160") (name "unconnected-(U18-PC3(ADC3)-Pad26)") (class "Default")
      (node (ref "U18") (pin "26") (pinfunction "PC3(ADC3)_26") (pintype "bidirectional"))
    )
    (net (code "161") (name "unconnected-(U19A-QE-Pad4)") (class "Default")
      (node (ref "U19") (pin "4") (pinfunction "QE_4") (pintype "tri_state"))
    )
    (net (code "162") (name "unconnected-(U19A-QF-Pad5)") (class "Default")
      (node (ref "U19") (pin "5") (pinfunction "QF_5") (pintype "tri_state"))
    )
    (net (code "163") (name "unconnected-(U19A-QG-Pad6)") (class "Default")
      (node (ref "U19") (pin "6") (pinfunction "QG_6") (pintype "tri_state"))
    )
    (net (code "164") (name "unconnected-(U19A-QH*-Pad9)") (class "Default")
      (node (ref "U19") (pin "9") (pinfunction "QH*_9") (pintype "tri_state"))
    )
    (net (code "165") (name "unconnected-(U19A-QH-Pad7)") (class "Default")
      (node (ref "U19") (pin "7") (pinfunction "QH_7") (pintype "tri_state"))
    )
    (net (code "166") (name "unconnected-(U21-CBUS2-Pad13)") (class "Default")
      (node (ref "U21") (pin "13") (pinfunction "CBUS2_13") (pintype "bidirectional"))
    )
    (net (code "167") (name "unconnected-(U21-CBUS3-Pad14)") (class "Default")
      (node (ref "U21") (pin "14") (pinfunction "CBUS3_14") (pintype "bidirectional"))
    )
    (net (code "168") (name "unconnected-(U21-CBUS4-Pad12)") (class "Default")
      (node (ref "U21") (pin "12") (pinfunction "CBUS4_12") (pintype "bidirectional"))
    )
    (net (code "169") (name "unconnected-(U21-OSCI-Pad27)") (class "Default")
      (node (ref "U21") (pin "27") (pinfunction "OSCI_27") (pintype "input"))
    )
    (net (code "170") (name "unconnected-(U21-OSCO-Pad28)") (class "Default")
      (node (ref "U21") (pin "28") (pinfunction "OSCO_28") (pintype "output"))
    )
    (net (code "171") (name "unconnected-(U21-~{CTS}-Pad11)") (class "Default")
      (node (ref "U21") (pin "11") (pinfunction "~{CTS}_11") (pintype "input"))
    )
    (net (code "172") (name "unconnected-(U21-~{DCD}-Pad10)") (class "Default")
      (node (ref "U21") (pin "10") (pinfunction "~{DCD}_10") (pintype "input"))
    )
    (net (code "173") (name "unconnected-(U21-~{DSR}-Pad9)") (class "Default")
      (node (ref "U21") (pin "9") (pinfunction "~{DSR}_9") (pintype "input"))
    )
    (net (code "174") (name "unconnected-(U21-~{RESET}-Pad19)") (class "Default")
      (node (ref "U21") (pin "19") (pinfunction "~{RESET}_19") (pintype "input"))
    )
    (net (code "175") (name "unconnected-(U21-~{RI}-Pad6)") (class "Default")
      (node (ref "U21") (pin "6") (pinfunction "~{RI}_6") (pintype "input"))
    )
    (net (code "176") (name "unconnected-(U22-CBUS0-Pad23)") (class "Default")
      (node (ref "U22") (pin "23") (pinfunction "CBUS0_23") (pintype "bidirectional"))
    )
    (net (code "177") (name "unconnected-(U22-CBUS1-Pad22)") (class "Default")
      (node (ref "U22") (pin "22") (pinfunction "CBUS1_22") (pintype "bidirectional"))
    )
    (net (code "178") (name "unconnected-(U22-CBUS2-Pad13)") (class "Default")
      (node (ref "U22") (pin "13") (pinfunction "CBUS2_13") (pintype "bidirectional"))
    )
    (net (code "179") (name "unconnected-(U22-CBUS3-Pad14)") (class "Default")
      (node (ref "U22") (pin "14") (pinfunction "CBUS3_14") (pintype "bidirectional"))
    )
    (net (code "180") (name "unconnected-(U22-CBUS4-Pad12)") (class "Default")
      (node (ref "U22") (pin "12") (pinfunction "CBUS4_12") (pintype "bidirectional"))
    )
    (net (code "181") (name "unconnected-(U22-OSCI-Pad27)") (class "Default")
      (node (ref "U22") (pin "27") (pinfunction "OSCI_27") (pintype "input"))
    )
    (net (code "182") (name "unconnected-(U22-OSCO-Pad28)") (class "Default")
      (node (ref "U22") (pin "28") (pinfunction "OSCO_28") (pintype "output"))
    )
    (net (code "183") (name "unconnected-(U22-~{CTS}-Pad11)") (class "Default")
      (node (ref "U22") (pin "11") (pinfunction "~{CTS}_11") (pintype "input"))
    )
    (net (code "184") (name "unconnected-(U22-~{DCD}-Pad10)") (class "Default")
      (node (ref "U22") (pin "10") (pinfunction "~{DCD}_10") (pintype "input"))
    )
    (net (code "185") (name "unconnected-(U22-~{DSR}-Pad9)") (class "Default")
      (node (ref "U22") (pin "9") (pinfunction "~{DSR}_9") (pintype "input"))
    )
    (net (code "186") (name "unconnected-(U22-~{DTR}-Pad2)") (class "Default")
      (node (ref "U22") (pin "2") (pinfunction "~{DTR}_2") (pintype "output"))
    )
    (net (code "187") (name "unconnected-(U22-~{RESET}-Pad19)") (class "Default")
      (node (ref "U22") (pin "19") (pinfunction "~{RESET}_19") (pintype "input"))
    )
    (net (code "188") (name "unconnected-(U22-~{RI}-Pad6)") (class "Default")
      (node (ref "U22") (pin "6") (pinfunction "~{RI}_6") (pintype "input"))
    )
  )
)
